# mini-48SE-0_7.net
KiCad netlist of a schematic drawn in EAGLE
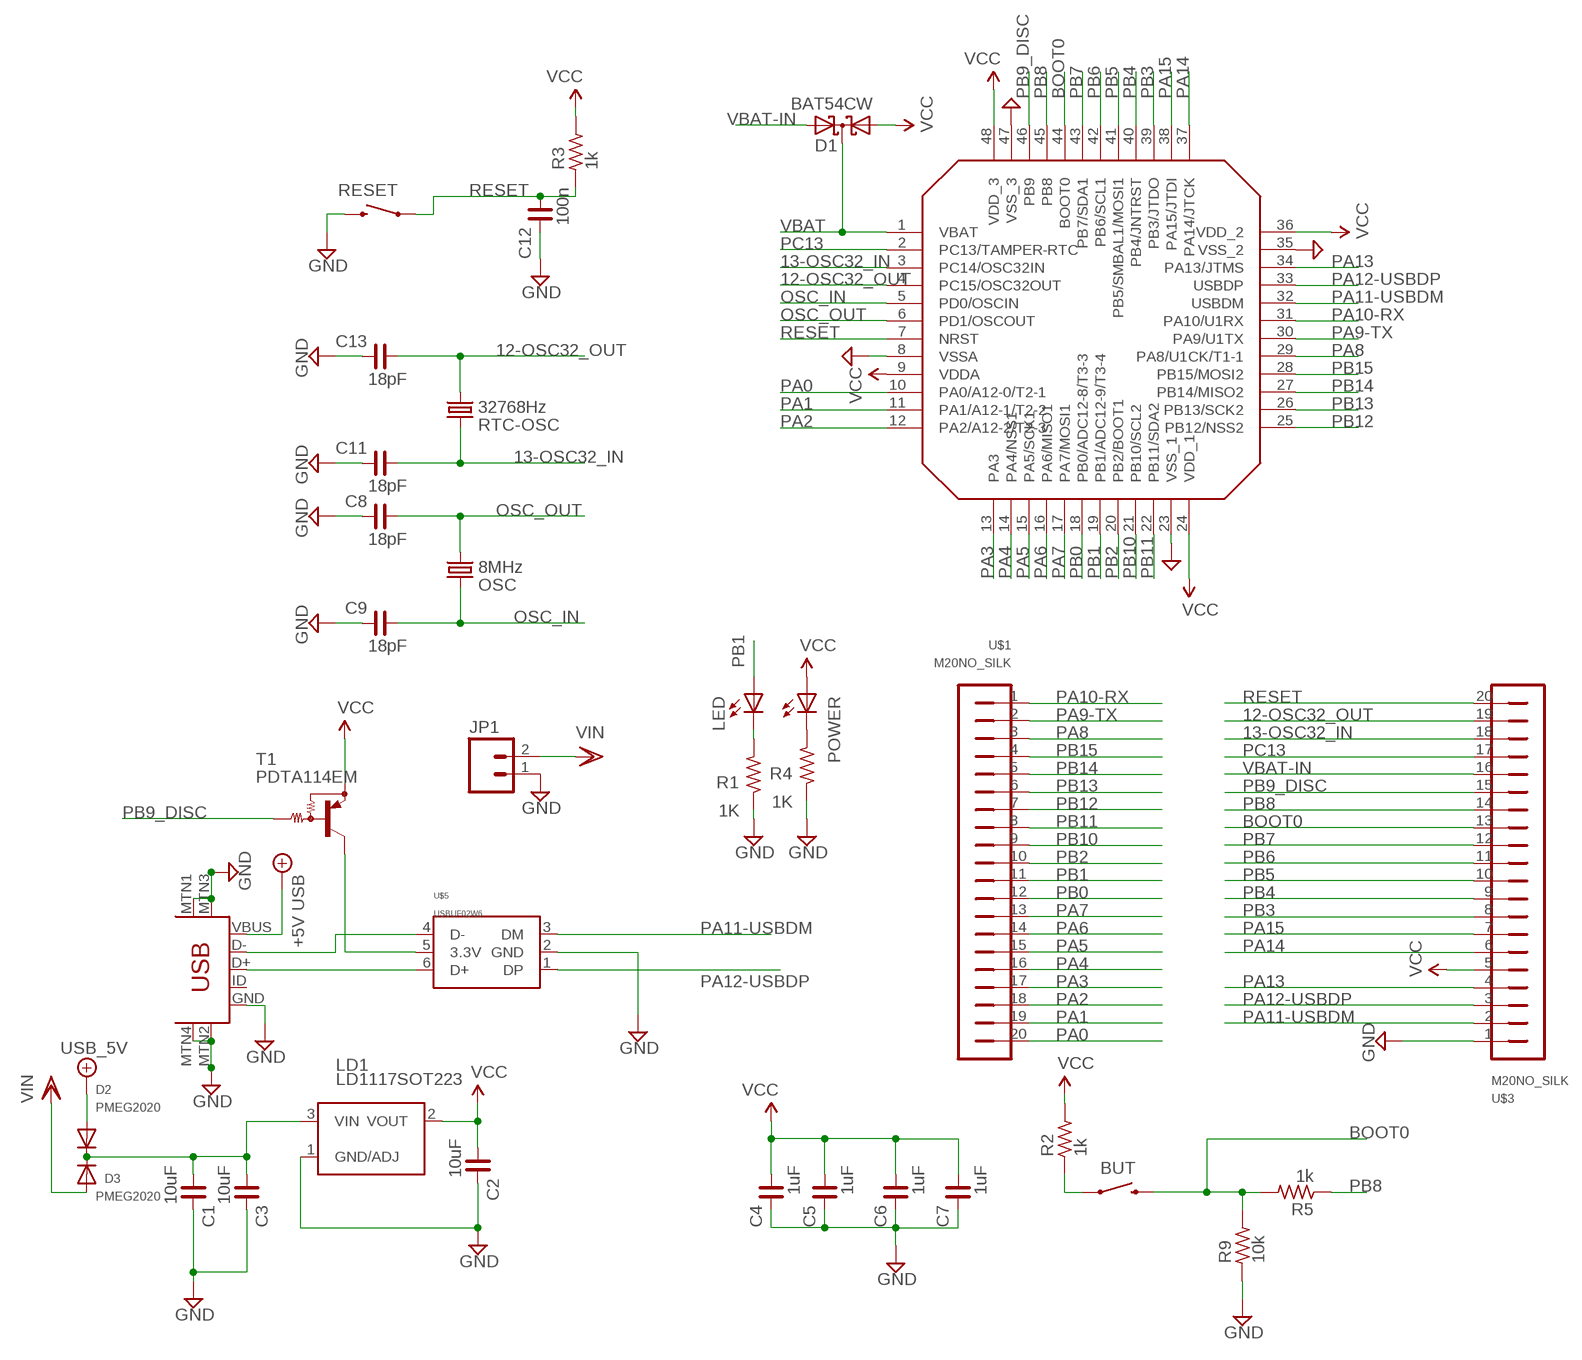
[diagram p0: schematic, sheet 1]

(export (version "E")
  (design (tool "Eeschema 10.0.6"))
  (components
    (comp (ref "BUT")
      (value "SWITCH-MOMENTARY-2TS-1185")
      (footprint "eagle-import:TS1185")
      (libsource (lib "eagle-import") (part "SWITCH-MOMENTARY-2TS-1185"))
    )
    (comp (ref "C1")
      (value "10uF")
      (footprint "eagle-import:C0603")
      (libsource (lib "eagle-import") (part "C_0603"))
    )
    (comp (ref "C2")
      (value "10uF")
      (footprint "eagle-import:C0805")
      (libsource (lib "eagle-import") (part "C_0805"))
    )
    (comp (ref "C3")
      (value "10uF")
      (footprint "eagle-import:C0603")
      (libsource (lib "eagle-import") (part "C_0603"))
    )
    (comp (ref "C4")
      (value "1uF")
      (footprint "eagle-import:C0603")
      (libsource (lib "eagle-import") (part "C_0603"))
    )
    (comp (ref "C5")
      (value "1uF")
      (footprint "eagle-import:C0603")
      (libsource (lib "eagle-import") (part "C_0603"))
    )
    (comp (ref "C6")
      (value "1uF")
      (footprint "eagle-import:C0603")
      (libsource (lib "eagle-import") (part "C_0603"))
    )
    (comp (ref "C7")
      (value "1uF")
      (footprint "eagle-import:C0603")
      (libsource (lib "eagle-import") (part "C_0603"))
    )
    (comp (ref "C8")
      (value "18pF")
      (footprint "eagle-import:C0603")
      (libsource (lib "eagle-import") (part "C_0603"))
    )
    (comp (ref "C9")
      (value "18pF")
      (footprint "eagle-import:C0603")
      (libsource (lib "eagle-import") (part "C_0603"))
    )
    (comp (ref "C11")
      (value "18pF")
      (footprint "eagle-import:C0603")
      (libsource (lib "eagle-import") (part "C_0603"))
    )
    (comp (ref "C12")
      (value "100n")
      (footprint "eagle-import:C0603")
      (libsource (lib "eagle-import") (part "C_0603"))
    )
    (comp (ref "C13")
      (value "18pF")
      (footprint "eagle-import:C0603")
      (libsource (lib "eagle-import") (part "C_0603"))
    )
    (comp (ref "D1")
      (value "BAT54CW")
      (footprint "eagle-import:SOT323R")
      (libsource (lib "eagle-import") (part "BAT54CW"))
    )
    (comp (ref "D2")
      (value "PMEG2020")
      (footprint "eagle-import:SOD-323")
      (libsource (lib "eagle-import") (part "DIODESOD-323"))
    )
    (comp (ref "D3")
      (value "PMEG2020")
      (footprint "eagle-import:SOD-323")
      (libsource (lib "eagle-import") (part "DIODESOD-323"))
    )
    (comp (ref "JP1")
      (value "M02-JST-2MM-SMT")
      (footprint "eagle-import:JST-2-SMD")
      (libsource (lib "eagle-import") (part "M02-JST-2MM-SMT"))
    )
    (comp (ref "LD1")
      (value "LD1117SOT223")
      (footprint "eagle-import:SOT223")
      (libsource (lib "eagle-import") (part "LD1117SOT223"))
    )
    (comp (ref "LED")
      (value "LED")
      (footprint "eagle-import:CHIPLED_1206")
      (libsource (lib "eagle-import") (part "LEDCHIPLED_1206"))
    )
    (comp (ref "OSC")
      (value "8MHz")
      (footprint "eagle-import:TC26H-M")
      (libsource (lib "eagle-import") (part "CRYSTALTC26HM"))
    )
    (comp (ref "POWER")
      (value "green")
      (footprint "eagle-import:CHIP-LED0603")
      (libsource (lib "eagle-import") (part "LEDCHIP-LED0603"))
    )
    (comp (ref "R1")
      (value "1K")
      (footprint "eagle-import:R0603")
      (libsource (lib "eagle-import") (part "R_0603"))
    )
    (comp (ref "R2")
      (value "1k")
      (footprint "eagle-import:R0603")
      (libsource (lib "eagle-import") (part "R_0603"))
    )
    (comp (ref "R3")
      (value "1k")
      (footprint "eagle-import:R0603")
      (libsource (lib "eagle-import") (part "R_0603"))
    )
    (comp (ref "R4")
      (value "1K")
      (footprint "eagle-import:R0603")
      (libsource (lib "eagle-import") (part "R_0603"))
    )
    (comp (ref "R5")
      (value "1k")
      (footprint "eagle-import:R0603")
      (libsource (lib "eagle-import") (part "R_0603"))
    )
    (comp (ref "R9")
      (value "10k")
      (footprint "eagle-import:R0603")
      (libsource (lib "eagle-import") (part "R_0603"))
    )
    (comp (ref "RESET")
      (value "SWITCH-MOMENTARY-2TS-1185")
      (footprint "eagle-import:TS1185")
      (libsource (lib "eagle-import") (part "SWITCH-MOMENTARY-2TS-1185"))
    )
    (comp (ref "RTC-OSC")
      (value "32768Hz")
      (footprint "eagle-import:TC26H-M")
      (libsource (lib "eagle-import") (part "CRYSTALTC26HM"))
    )
    (comp (ref "T1")
      (value "PDTA114EM")
      (footprint "eagle-import:SOT323R")
      (libsource (lib "eagle-import") (part "PNP-DRIVERSOT323"))
    )
    (comp (ref "U$1")
      (value "M20NO_SILK")
      (footprint "eagle-import:1X20_NO_SILK")
      (libsource (lib "eagle-import") (part "M20NO_SILK"))
    )
    (comp (ref "U$3")
      (value "M20NO_SILK")
      (footprint "eagle-import:1X20_NO_SILK")
      (libsource (lib "eagle-import") (part "M20NO_SILK"))
    )
    (comp (ref "U$4")
      (value "STM32F103_48")
      (footprint "eagle-import:LQFP48-7X7")
      (libsource (lib "eagle-import") (part "STM32F103_48"))
    )
    (comp (ref "U$5")
      (value "USBUF02W6")
      (footprint "eagle-import:SC70-6")
      (libsource (lib "eagle-import") (part "USBUF02W6"))
    )
    (comp (ref "USB")
      (value "USB-MINIB-5PIN")
      (footprint "eagle-import:USB-MINIB")
      (libsource (lib "eagle-import") (part "USB-MINIB-5PIN"))
    )
  )
  (nets
    (net (code "1") (name "+5V USB") (class "Default")
      (node (ref "D2") (pin "A") (pinfunction "A_A") (pintype "passive"))
      (node (ref "USB") (pin "VBUS") (pinfunction "VBUS_VBUS") (pintype "bidirectional"))
    )
    (net (code "2") (name "/12-OSC32_OUT") (class "Default")
      (node (ref "C13") (pin "1") (pinfunction "1_1") (pintype "passive"))
      (node (ref "RTC-OSC") (pin "1") (pinfunction "1_1") (pintype "passive"))
      (node (ref "U$3") (pin "19") (pinfunction "P$19_19") (pintype "bidirectional"))
      (node (ref "U$4") (pin "4") (pinfunction "PC15/OSC32OUT_4") (pintype "bidirectional"))
    )
    (net (code "3") (name "/13-OSC32_IN") (class "Default")
      (node (ref "C11") (pin "1") (pinfunction "1_1") (pintype "passive"))
      (node (ref "RTC-OSC") (pin "2") (pinfunction "2_2") (pintype "passive"))
      (node (ref "U$3") (pin "18") (pinfunction "P$18_18") (pintype "bidirectional"))
      (node (ref "U$4") (pin "3") (pinfunction "PC14/OSC32IN_3") (pintype "bidirectional"))
    )
    (net (code "4") (name "/BOOT0") (class "Default")
      (node (ref "BUT") (pin "2") (pinfunction "2_2") (pintype "passive"))
      (node (ref "R5") (pin "2") (pinfunction "2_2") (pintype "passive"))
      (node (ref "R9") (pin "2") (pinfunction "2_2") (pintype "passive"))
      (node (ref "U$3") (pin "13") (pinfunction "P$13_13") (pintype "bidirectional"))
      (node (ref "U$4") (pin "44") (pinfunction "BOOT0_44") (pintype "bidirectional"))
    )
    (net (code "5") (name "/OSC_IN") (class "Default")
      (node (ref "C9") (pin "1") (pinfunction "1_1") (pintype "passive"))
      (node (ref "OSC") (pin "2") (pinfunction "2_2") (pintype "passive"))
      (node (ref "U$4") (pin "5") (pinfunction "PD0/OSCIN_5") (pintype "bidirectional"))
    )
    (net (code "6") (name "/OSC_OUT") (class "Default")
      (node (ref "C8") (pin "1") (pinfunction "1_1") (pintype "passive"))
      (node (ref "OSC") (pin "1") (pinfunction "1_1") (pintype "passive"))
      (node (ref "U$4") (pin "6") (pinfunction "PD1/OSCOUT_6") (pintype "bidirectional"))
    )
    (net (code "7") (name "/PA0") (class "Default")
      (node (ref "U$1") (pin "20") (pinfunction "P$20_20") (pintype "bidirectional"))
      (node (ref "U$4") (pin "10") (pinfunction "PA0/A12-0/T2-1_10") (pintype "bidirectional"))
    )
    (net (code "8") (name "/PA1") (class "Default")
      (node (ref "U$1") (pin "19") (pinfunction "P$19_19") (pintype "bidirectional"))
      (node (ref "U$4") (pin "11") (pinfunction "PA1/A12-1/T2-2_11") (pintype "bidirectional"))
    )
    (net (code "9") (name "/PA2") (class "Default")
      (node (ref "U$1") (pin "18") (pinfunction "P$18_18") (pintype "bidirectional"))
      (node (ref "U$4") (pin "12") (pinfunction "PA2/A12-2/T2-3_12") (pintype "bidirectional"))
    )
    (net (code "10") (name "/PA3") (class "Default")
      (node (ref "U$1") (pin "17") (pinfunction "P$17_17") (pintype "bidirectional"))
      (node (ref "U$4") (pin "13") (pinfunction "PA3_13") (pintype "bidirectional"))
    )
    (net (code "11") (name "/PA4") (class "Default")
      (node (ref "U$1") (pin "16") (pinfunction "P$16_16") (pintype "bidirectional"))
      (node (ref "U$4") (pin "14") (pinfunction "PA4/NSS1_14") (pintype "bidirectional"))
    )
    (net (code "12") (name "/PA5") (class "Default")
      (node (ref "U$1") (pin "15") (pinfunction "P$15_15") (pintype "bidirectional"))
      (node (ref "U$4") (pin "15") (pinfunction "PA5/SCK1_15") (pintype "bidirectional"))
    )
    (net (code "13") (name "/PA6") (class "Default")
      (node (ref "U$1") (pin "14") (pinfunction "P$14_14") (pintype "bidirectional"))
      (node (ref "U$4") (pin "16") (pinfunction "PA6/MISO1_16") (pintype "bidirectional"))
    )
    (net (code "14") (name "/PA7") (class "Default")
      (node (ref "U$1") (pin "13") (pinfunction "P$13_13") (pintype "bidirectional"))
      (node (ref "U$4") (pin "17") (pinfunction "PA7/MOSI1_17") (pintype "bidirectional"))
    )
    (net (code "15") (name "/PA8") (class "Default")
      (node (ref "U$1") (pin "3") (pinfunction "P$3_3") (pintype "bidirectional"))
      (node (ref "U$4") (pin "29") (pinfunction "PA8/U1CK/T1-1_29") (pintype "bidirectional"))
    )
    (net (code "16") (name "/PA9-TX") (class "Default")
      (node (ref "U$1") (pin "2") (pinfunction "P$2_2") (pintype "bidirectional"))
      (node (ref "U$4") (pin "30") (pinfunction "PA9/U1TX_30") (pintype "bidirectional"))
    )
    (net (code "17") (name "/PA10-RX") (class "Default")
      (node (ref "U$1") (pin "1") (pinfunction "P$1_1") (pintype "bidirectional"))
      (node (ref "U$4") (pin "31") (pinfunction "PA10/U1RX_31") (pintype "bidirectional"))
    )
    (net (code "18") (name "/PA11-USBDM") (class "Default")
      (node (ref "U$3") (pin "2") (pinfunction "P$2_2") (pintype "bidirectional"))
      (node (ref "U$4") (pin "32") (pinfunction "USBDM_32") (pintype "bidirectional"))
      (node (ref "U$5") (pin "3") (pinfunction "DM_3") (pintype "bidirectional"))
    )
    (net (code "19") (name "/PA12-USBDP") (class "Default")
      (node (ref "U$3") (pin "3") (pinfunction "P$3_3") (pintype "bidirectional"))
      (node (ref "U$4") (pin "33") (pinfunction "USBDP_33") (pintype "bidirectional"))
      (node (ref "U$5") (pin "1") (pinfunction "DP_1") (pintype "bidirectional"))
    )
    (net (code "20") (name "/PA13") (class "Default")
      (node (ref "U$3") (pin "4") (pinfunction "P$4_4") (pintype "bidirectional"))
      (node (ref "U$4") (pin "34") (pinfunction "PA13/JTMS_34") (pintype "bidirectional"))
    )
    (net (code "21") (name "/PA14") (class "Default")
      (node (ref "U$3") (pin "6") (pinfunction "P$6_6") (pintype "bidirectional"))
      (node (ref "U$4") (pin "37") (pinfunction "PA14/JTCK_37") (pintype "bidirectional"))
    )
    (net (code "22") (name "/PA15") (class "Default")
      (node (ref "U$3") (pin "7") (pinfunction "P$7_7") (pintype "bidirectional"))
      (node (ref "U$4") (pin "38") (pinfunction "PA15/JTDI_38") (pintype "bidirectional"))
    )
    (net (code "23") (name "/PB0") (class "Default")
      (node (ref "U$1") (pin "12") (pinfunction "P$12_12") (pintype "bidirectional"))
      (node (ref "U$4") (pin "18") (pinfunction "PB0/ADC12-8/T3-3_18") (pintype "bidirectional"))
    )
    (net (code "24") (name "/PB1") (class "Default")
      (node (ref "LED") (pin "A") (pinfunction "A_A") (pintype "passive"))
      (node (ref "U$1") (pin "11") (pinfunction "P$11_11") (pintype "bidirectional"))
      (node (ref "U$4") (pin "19") (pinfunction "PB1/ADC12-9/T3-4_19") (pintype "bidirectional"))
    )
    (net (code "25") (name "/PB2") (class "Default")
      (node (ref "U$1") (pin "10") (pinfunction "P$10_10") (pintype "bidirectional"))
      (node (ref "U$4") (pin "20") (pinfunction "PB2/BOOT1_20") (pintype "bidirectional"))
    )
    (net (code "26") (name "/PB3") (class "Default")
      (node (ref "U$3") (pin "8") (pinfunction "P$8_8") (pintype "bidirectional"))
      (node (ref "U$4") (pin "39") (pinfunction "PB3/JTDO_39") (pintype "bidirectional"))
    )
    (net (code "27") (name "/PB4") (class "Default")
      (node (ref "U$3") (pin "9") (pinfunction "P$9_9") (pintype "bidirectional"))
      (node (ref "U$4") (pin "40") (pinfunction "PB4/JNTRST_40") (pintype "bidirectional"))
    )
    (net (code "28") (name "/PB5") (class "Default")
      (node (ref "U$3") (pin "10") (pinfunction "P$10_10") (pintype "bidirectional"))
      (node (ref "U$4") (pin "41") (pinfunction "PB5/SMBAL1/MOSI1_41") (pintype "bidirectional"))
    )
    (net (code "29") (name "/PB6") (class "Default")
      (node (ref "U$3") (pin "11") (pinfunction "P$11_11") (pintype "bidirectional"))
      (node (ref "U$4") (pin "42") (pinfunction "PB6/SCL1_42") (pintype "bidirectional"))
    )
    (net (code "30") (name "/PB7") (class "Default")
      (node (ref "U$3") (pin "12") (pinfunction "P$12_12") (pintype "bidirectional"))
      (node (ref "U$4") (pin "43") (pinfunction "PB7/SDA1_43") (pintype "bidirectional"))
    )
    (net (code "31") (name "/PB8") (class "Default")
      (node (ref "R5") (pin "1") (pinfunction "1_1") (pintype "passive"))
      (node (ref "U$3") (pin "14") (pinfunction "P$14_14") (pintype "bidirectional"))
      (node (ref "U$4") (pin "45") (pinfunction "PB8_45") (pintype "bidirectional"))
    )
    (net (code "32") (name "/PB9_DISC") (class "Default")
      (node (ref "T1") (pin "1") (pinfunction "B_1") (pintype "passive"))
      (node (ref "U$3") (pin "15") (pinfunction "P$15_15") (pintype "bidirectional"))
      (node (ref "U$4") (pin "46") (pinfunction "PB9_46") (pintype "bidirectional"))
    )
    (net (code "33") (name "/PB10") (class "Default")
      (node (ref "U$1") (pin "9") (pinfunction "P$9_9") (pintype "bidirectional"))
      (node (ref "U$4") (pin "21") (pinfunction "PB10/SCL2_21") (pintype "bidirectional"))
    )
    (net (code "34") (name "/PB11") (class "Default")
      (node (ref "U$1") (pin "8") (pinfunction "P$8_8") (pintype "bidirectional"))
      (node (ref "U$4") (pin "22") (pinfunction "PB11/SDA2_22") (pintype "bidirectional"))
    )
    (net (code "35") (name "/PB12") (class "Default")
      (node (ref "U$1") (pin "7") (pinfunction "P$7_7") (pintype "bidirectional"))
      (node (ref "U$4") (pin "25") (pinfunction "PB12/NSS2_25") (pintype "bidirectional"))
    )
    (net (code "36") (name "/PB13") (class "Default")
      (node (ref "U$1") (pin "6") (pinfunction "P$6_6") (pintype "bidirectional"))
      (node (ref "U$4") (pin "26") (pinfunction "PB13/SCK2_26") (pintype "bidirectional"))
    )
    (net (code "37") (name "/PB14") (class "Default")
      (node (ref "U$1") (pin "5") (pinfunction "P$5_5") (pintype "bidirectional"))
      (node (ref "U$4") (pin "27") (pinfunction "PB14/MISO2_27") (pintype "bidirectional"))
    )
    (net (code "38") (name "/PB15") (class "Default")
      (node (ref "U$1") (pin "4") (pinfunction "P$4_4") (pintype "bidirectional"))
      (node (ref "U$4") (pin "28") (pinfunction "PB15/MOSI2_28") (pintype "bidirectional"))
    )
    (net (code "39") (name "/PC13") (class "Default")
      (node (ref "U$3") (pin "17") (pinfunction "P$17_17") (pintype "bidirectional"))
      (node (ref "U$4") (pin "2") (pinfunction "PC13/TAMPER-RTC_2") (pintype "bidirectional"))
    )
    (net (code "40") (name "/RESET") (class "Default")
      (node (ref "C12") (pin "1") (pinfunction "1_1") (pintype "passive"))
      (node (ref "R3") (pin "1") (pinfunction "1_1") (pintype "passive"))
      (node (ref "RESET") (pin "1") (pinfunction "1_1") (pintype "passive"))
      (node (ref "U$3") (pin "20") (pinfunction "P$20_20") (pintype "bidirectional"))
      (node (ref "U$4") (pin "7") (pinfunction "NRST_7") (pintype "bidirectional"))
    )
    (net (code "41") (name "/VBAT") (class "Default")
      (node (ref "D1") (pin "3") (pinfunction "CC_3") (pintype "passive"))
      (node (ref "U$4") (pin "1") (pinfunction "VBAT_1") (pintype "bidirectional"))
    )
    (net (code "42") (name "/VBAT-IN") (class "Default")
      (node (ref "D1") (pin "2") (pinfunction "A2_2") (pintype "passive"))
      (node (ref "U$3") (pin "16") (pinfunction "P$16_16") (pintype "bidirectional"))
    )
    (net (code "43") (name "GND") (class "Default")
      (node (ref "C1") (pin "2") (pinfunction "2_2") (pintype "passive"))
      (node (ref "C11") (pin "2") (pinfunction "2_2") (pintype "passive"))
      (node (ref "C12") (pin "2") (pinfunction "2_2") (pintype "passive"))
      (node (ref "C13") (pin "2") (pinfunction "2_2") (pintype "passive"))
      (node (ref "C2") (pin "2") (pinfunction "2_2") (pintype "passive"))
      (node (ref "C3") (pin "2") (pinfunction "2_2") (pintype "passive"))
      (node (ref "C4") (pin "2") (pinfunction "2_2") (pintype "passive"))
      (node (ref "C5") (pin "2") (pinfunction "2_2") (pintype "passive"))
      (node (ref "C6") (pin "2") (pinfunction "2_2") (pintype "passive"))
      (node (ref "C7") (pin "2") (pinfunction "2_2") (pintype "passive"))
      (node (ref "C8") (pin "2") (pinfunction "2_2") (pintype "passive"))
      (node (ref "C9") (pin "2") (pinfunction "2_2") (pintype "passive"))
      (node (ref "JP1") (pin "1") (pinfunction "1_1") (pintype "passive"))
      (node (ref "LD1") (pin "1") (pinfunction "GND/ADJ_1") (pintype "bidirectional"))
      (node (ref "R1") (pin "1") (pinfunction "1_1") (pintype "passive"))
      (node (ref "R4") (pin "1") (pinfunction "1_1") (pintype "passive"))
      (node (ref "R9") (pin "1") (pinfunction "1_1") (pintype "passive"))
      (node (ref "RESET") (pin "2") (pinfunction "2_2") (pintype "passive"))
      (node (ref "U$3") (pin "1") (pinfunction "P$1_1") (pintype "bidirectional"))
      (node (ref "U$4") (pin "23") (pinfunction "VSS_1_23") (pintype "bidirectional"))
      (node (ref "U$4") (pin "35") (pinfunction "VSS_2_35") (pintype "bidirectional"))
      (node (ref "U$4") (pin "47") (pinfunction "VSS_3_47") (pintype "bidirectional"))
      (node (ref "U$4") (pin "8") (pinfunction "VSSA_8") (pintype "bidirectional"))
      (node (ref "U$5") (pin "2") (pinfunction "GND_2") (pintype "bidirectional"))
      (node (ref "USB") (pin "GND") (pinfunction "GND_GND") (pintype "bidirectional"))
      (node (ref "USB") (pin "MTN1") (pinfunction "MTN2_MTN1") (pintype "bidirectional"))
      (node (ref "USB") (pin "MTN2") (pinfunction "MTN3_MTN2") (pintype "bidirectional"))
      (node (ref "USB") (pin "MTN3") (pinfunction "MTN1_MTN3") (pintype "bidirectional"))
      (node (ref "USB") (pin "MTN4") (pinfunction "MTN4_MTN4") (pintype "bidirectional"))
    )
    (net (code "44") (name "Net-(BUT-Pad1)") (class "Default")
      (node (ref "BUT") (pin "1") (pinfunction "1_1") (pintype "passive"))
      (node (ref "R2") (pin "1") (pinfunction "1_1") (pintype "passive"))
    )
    (net (code "45") (name "Net-(LD1-VIN)") (class "Default")
      (node (ref "C1") (pin "1") (pinfunction "1_1") (pintype "passive"))
      (node (ref "C3") (pin "1") (pinfunction "1_1") (pintype "passive"))
      (node (ref "D2") (pin "C") (pinfunction "C_C") (pintype "passive"))
      (node (ref "D3") (pin "C") (pinfunction "C_C") (pintype "passive"))
      (node (ref "LD1") (pin "3") (pinfunction "VIN_3") (pintype "bidirectional"))
    )
    (net (code "46") (name "Net-(LED-PadC)") (class "Default")
      (node (ref "LED") (pin "C") (pinfunction "C_C") (pintype "passive"))
      (node (ref "R1") (pin "2") (pinfunction "2_2") (pintype "passive"))
    )
    (net (code "47") (name "Net-(POWER-PadC)") (class "Default")
      (node (ref "POWER") (pin "C") (pinfunction "C_C") (pintype "passive"))
      (node (ref "R4") (pin "2") (pinfunction "2_2") (pintype "passive"))
    )
    (net (code "48") (name "Net-(T1-C)") (class "Default")
      (node (ref "T1") (pin "3") (pinfunction "C_3") (pintype "passive"))
      (node (ref "U$5") (pin "5") (pinfunction "3.3V_5") (pintype "bidirectional"))
    )
    (net (code "49") (name "Net-(U$5-D+)") (class "Default")
      (node (ref "U$5") (pin "6") (pinfunction "D+_6") (pintype "bidirectional"))
      (node (ref "USB") (pin "D+") (pinfunction "D+_D+") (pintype "bidirectional"))
    )
    (net (code "50") (name "Net-(U$5-D-)") (class "Default")
      (node (ref "U$5") (pin "4") (pinfunction "D-_4") (pintype "bidirectional"))
      (node (ref "USB") (pin "D-") (pinfunction "D-_D-") (pintype "bidirectional"))
    )
    (net (code "51") (name "VCC") (class "Default")
      (node (ref "C2") (pin "1") (pinfunction "1_1") (pintype "passive"))
      (node (ref "C4") (pin "1") (pinfunction "1_1") (pintype "passive"))
      (node (ref "C5") (pin "1") (pinfunction "1_1") (pintype "passive"))
      (node (ref "C6") (pin "1") (pinfunction "1_1") (pintype "passive"))
      (node (ref "C7") (pin "1") (pinfunction "1_1") (pintype "passive"))
      (node (ref "D1") (pin "1") (pinfunction "A1_1") (pintype "passive"))
      (node (ref "LD1") (pin "2") (pinfunction "VOUT_2") (pintype "bidirectional"))
      (node (ref "POWER") (pin "A") (pinfunction "A_A") (pintype "passive"))
      (node (ref "R2") (pin "2") (pinfunction "2_2") (pintype "passive"))
      (node (ref "R3") (pin "2") (pinfunction "2_2") (pintype "passive"))
      (node (ref "T1") (pin "2") (pinfunction "E_2") (pintype "passive"))
      (node (ref "U$3") (pin "5") (pinfunction "P$5_5") (pintype "bidirectional"))
      (node (ref "U$4") (pin "24") (pinfunction "VDD_1_24") (pintype "bidirectional"))
      (node (ref "U$4") (pin "36") (pinfunction "VDD_2_36") (pintype "bidirectional"))
      (node (ref "U$4") (pin "48") (pinfunction "VDD_3_48") (pintype "bidirectional"))
      (node (ref "U$4") (pin "9") (pinfunction "VDDA_9") (pintype "bidirectional"))
    )
    (net (code "52") (name "VIN") (class "Default")
      (node (ref "D3") (pin "A") (pinfunction "A_A") (pintype "passive"))
      (node (ref "JP1") (pin "2") (pinfunction "2_2") (pintype "passive"))
    )
    (net (code "53") (name "unconnected-(USB-PadID)") (class "Default")
      (node (ref "USB") (pin "ID") (pinfunction "ID_ID") (pintype "bidirectional"))
    )
  )
)
